# Sheet1.net
KiCad netlist of a schematic drawn in Altium Designer
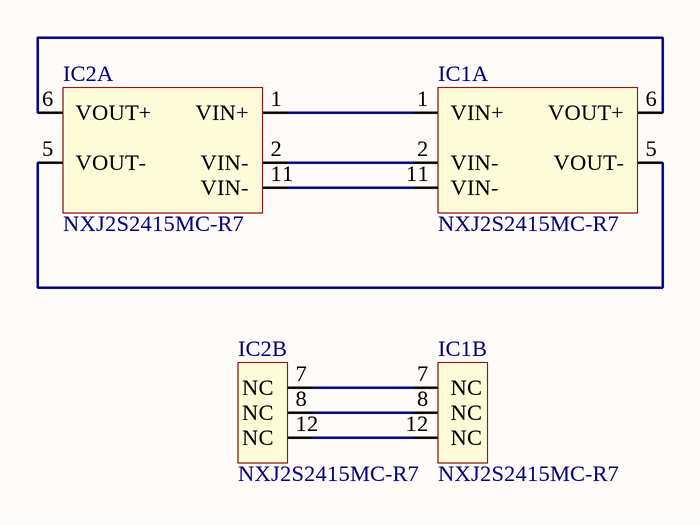
[diagram p0: Sheet1.SchDoc]

(export (version "E")
  (design (tool "Eeschema 10.0.6"))
  (components
    (comp (ref "IC1")
      (value "NXJ2S2415MC-R7")
      (footprint "DCDC")
      (description "Isolated DC/DC Converters - SMD 21.6V TO 26.4V IN 15V OUT")
      (fields (field (name "MANUFACTURER") "Murata") (field (name "CREATED FROM") "VStarost"))
      (libsource (lib "user") (part "DCDC"))
    )
    (comp (ref "IC2")
      (value "NXJ2S2415MC-R7")
      (footprint "DCDC")
      (description "Isolated DC/DC Converters - SMD 21.6V TO 26.4V IN 15V OUT")
      (fields (field (name "MANUFACTURER") "Murata") (field (name "CREATED FROM") "VStarost"))
      (libsource (lib "") (part "DCDC_1"))
    )
  )
  (nets
    (net (code "1") (name "Net-(IC1A-VIN+)") (class "Default")
      (node (ref "IC1") (pin "1") (pinfunction "VIN+_1") (pintype "passive"))
      (node (ref "IC2") (pin "1") (pinfunction "VIN+_1") (pintype "passive"))
    )
    (net (code "2") (name "Net-(IC1A-VIN--Pad2)") (class "Default")
      (node (ref "IC1") (pin "2") (pinfunction "VIN-_2") (pintype "passive"))
      (node (ref "IC2") (pin "2") (pinfunction "VIN-_2") (pintype "passive"))
    )
    (net (code "3") (name "Net-(IC1A-VIN--Pad11)") (class "Default")
      (node (ref "IC1") (pin "11") (pinfunction "VIN-_11") (pintype "passive"))
      (node (ref "IC2") (pin "11") (pinfunction "VIN-_11") (pintype "passive"))
    )
    (net (code "4") (name "Net-(IC1A-VOUT+)") (class "Default")
      (node (ref "IC1") (pin "6") (pinfunction "VOUT+_6") (pintype "passive"))
      (node (ref "IC2") (pin "6") (pinfunction "VOUT+_6") (pintype "passive"))
    )
    (net (code "5") (name "Net-(IC1A-VOUT-)") (class "Default")
      (node (ref "IC1") (pin "5") (pinfunction "VOUT-_5") (pintype "passive"))
      (node (ref "IC2") (pin "5") (pinfunction "VOUT-_5") (pintype "passive"))
    )
    (net (code "6") (name "Net-(IC1B-NC-Pad7)") (class "Default")
      (node (ref "IC1") (pin "7") (pinfunction "NC_7") (pintype "passive"))
      (node (ref "IC2") (pin "7") (pinfunction "NC_7") (pintype "passive"))
    )
    (net (code "7") (name "Net-(IC1B-NC-Pad8)") (class "Default")
      (node (ref "IC1") (pin "8") (pinfunction "NC_8") (pintype "passive"))
      (node (ref "IC2") (pin "8") (pinfunction "NC_8") (pintype "passive"))
    )
    (net (code "8") (name "Net-(IC1B-NC-Pad12)") (class "Default")
      (node (ref "IC1") (pin "12") (pinfunction "NC_12") (pintype "passive"))
      (node (ref "IC2") (pin "12") (pinfunction "NC_12") (pintype "passive"))
    )
  )
)
